# VS1005-Pico_2024-02-05.net
KiCad netlist of a schematic drawn in Altium Designer
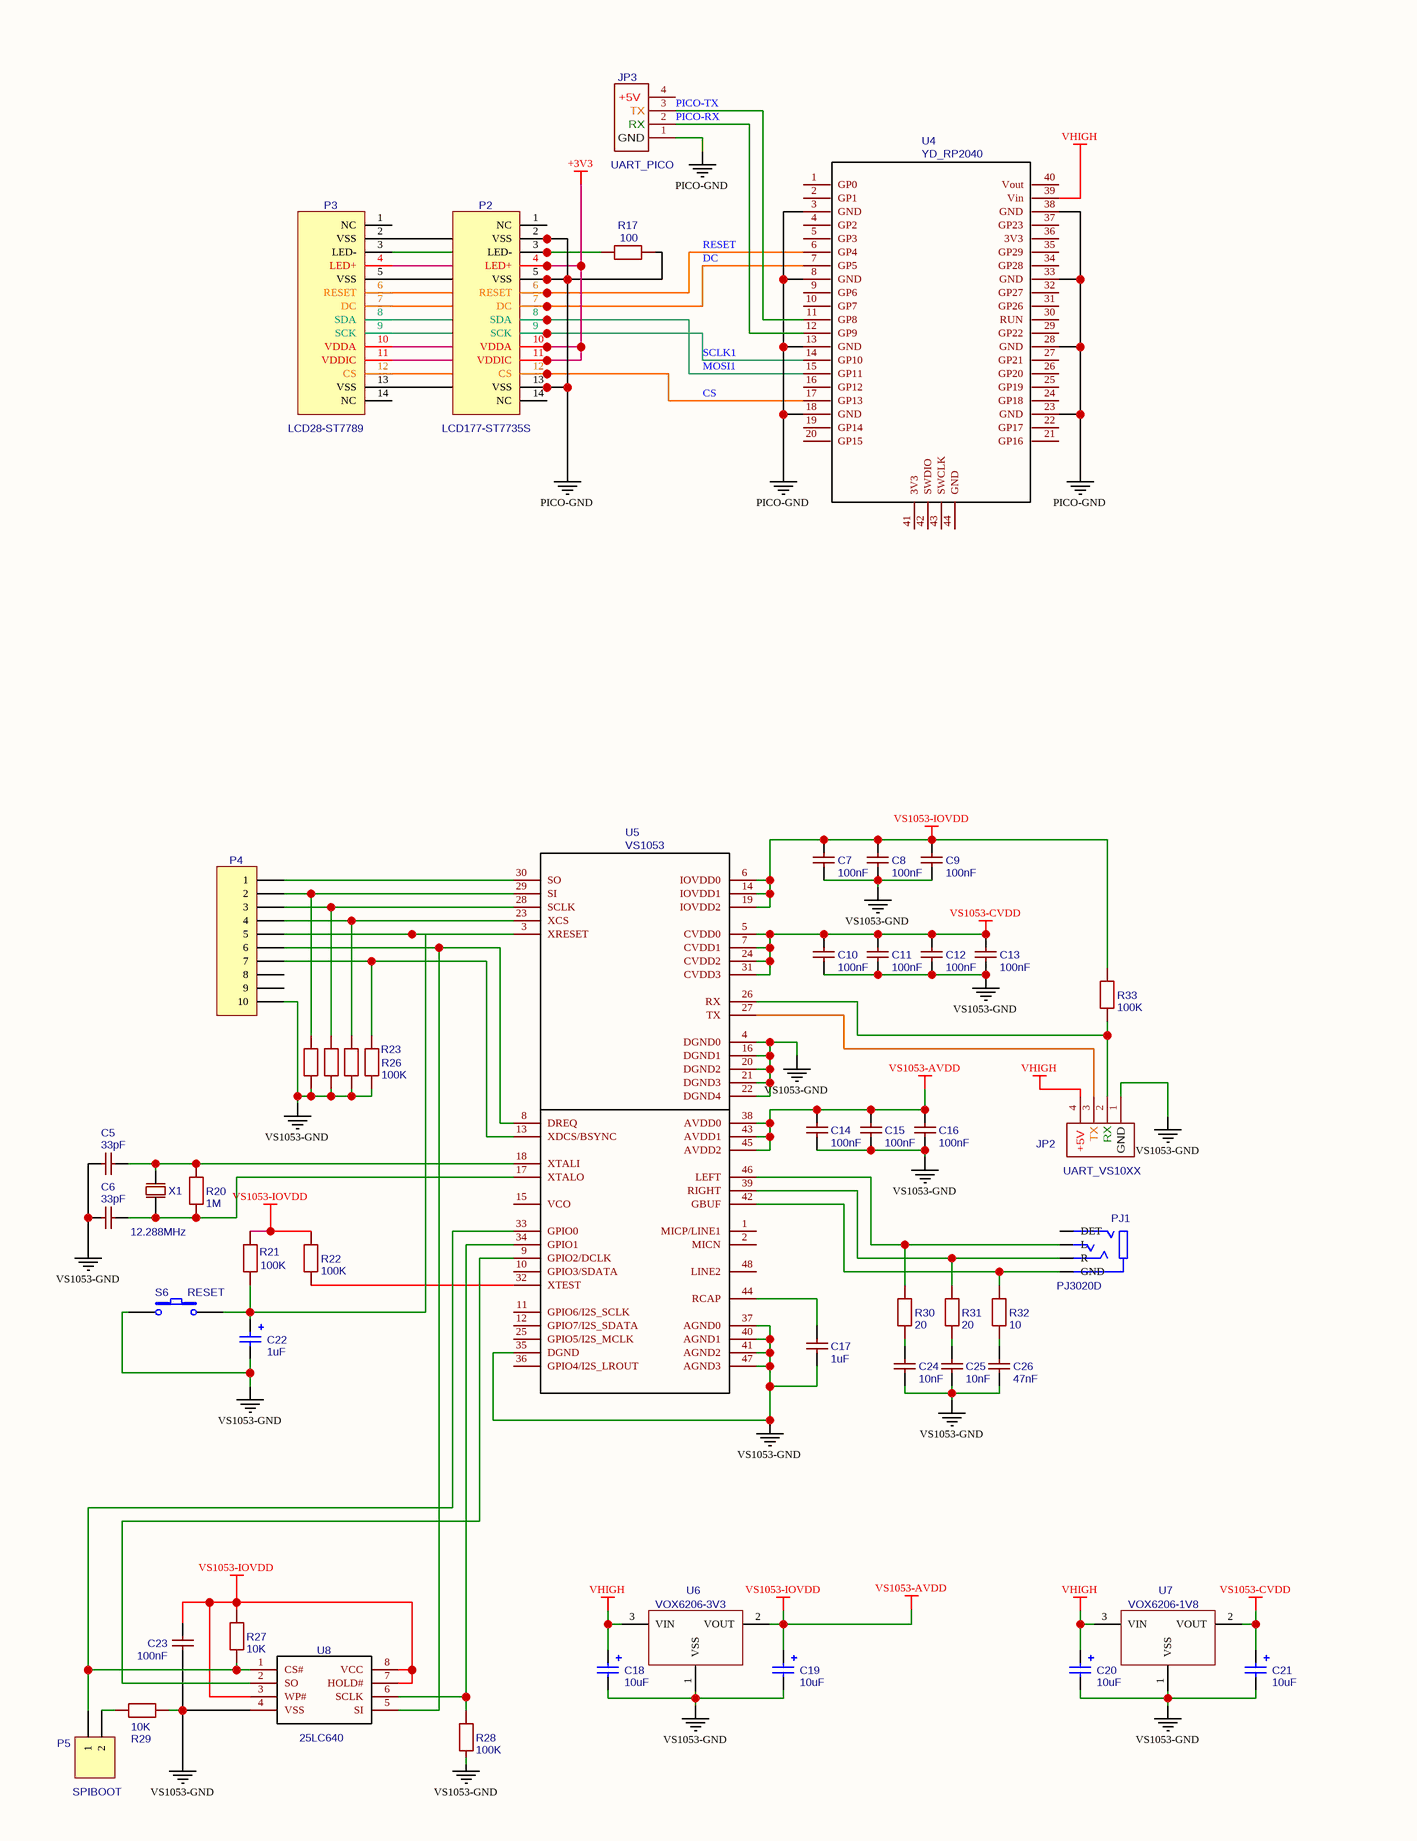
[diagram p0: VS1005-Pico_2024-02-05.schdoc, left]
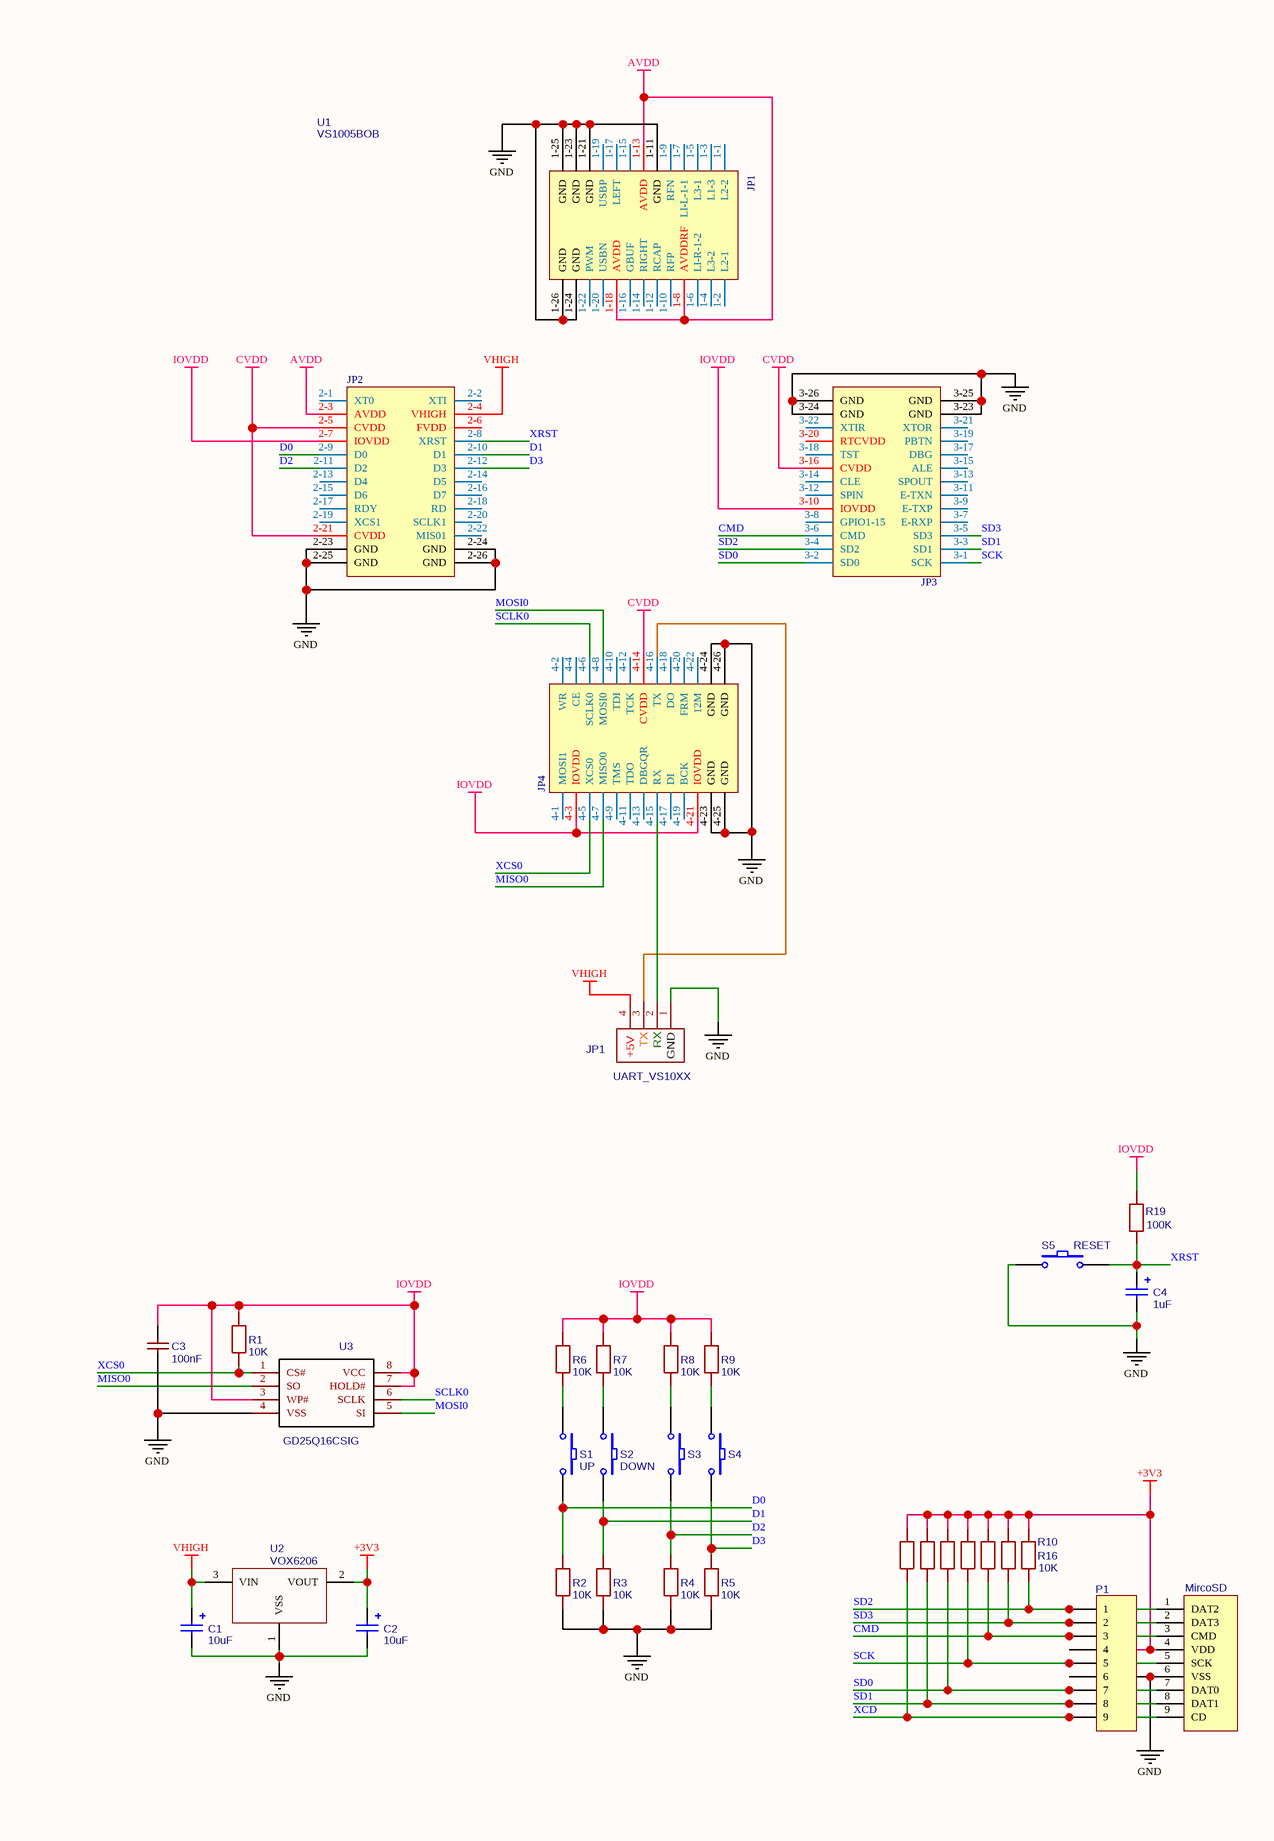
[diagram p1: VS1005-Pico_2024-02-05.schdoc, right]

(export (version "E")
  (design (tool "Eeschema 10.0.6"))
  (components
    (comp (ref "C1")
      (value "10uF")
      (fields (field (name "PUBLISHER") "Altium Limited") (field (name "CONTRIBUTOR") "kmok163"))
      (libsource (lib "altium-import") (part "root_0_10uF_"))
    )
    (comp (ref "C2")
      (value "10uF")
      (fields (field (name "PUBLISHER") "Altium Limited") (field (name "CONTRIBUTOR") "kmok163"))
      (libsource (lib "altium-import") (part "root_0_10uF_"))
    )
    (comp (ref "C3")
      (value "100nF")
      (fields
        (field (name "MANUFACTURER PART") "CC0805KRX7R9BB104")
        (field (name "MANUFACTURER") "YAGEO")
        (field (name "CONTRIBUTOR") "fen-1")
      )
      (libsource (lib "altium-import") (part "root_3_100nF_"))
    )
    (comp (ref "C4")
      (value "1uF")
      (fields (field (name "PUBLISHER") "Altium Limited") (field (name "CONTRIBUTOR") "kmok163"))
      (libsource (lib "altium-import") (part "root_0_1uF_"))
    )
    (comp (ref "C5")
      (value "33pF")
      (fields
        (field (name "MANUFACTURER PART") "CC0805KRX7R9BB104")
        (field (name "MANUFACTURER") "YAGEO")
        (field (name "CONTRIBUTOR") "fen-1")
      )
      (libsource (lib "altium-import") (part "root_2_33pF_"))
    )
    (comp (ref "C6")
      (value "33pF")
      (fields
        (field (name "MANUFACTURER PART") "CC0805KRX7R9BB104")
        (field (name "MANUFACTURER") "YAGEO")
        (field (name "CONTRIBUTOR") "fen-1")
      )
      (libsource (lib "altium-import") (part "root_2_33pF_"))
    )
    (comp (ref "C7")
      (value "100nF")
      (fields
        (field (name "MANUFACTURER PART") "CC0805KRX7R9BB104")
        (field (name "MANUFACTURER") "YAGEO")
        (field (name "CONTRIBUTOR") "fen-1")
      )
      (libsource (lib "altium-import") (part "root_3_100nF_"))
    )
    (comp (ref "C8")
      (value "100nF")
      (fields
        (field (name "MANUFACTURER PART") "CC0805KRX7R9BB104")
        (field (name "MANUFACTURER") "YAGEO")
        (field (name "CONTRIBUTOR") "fen-1")
      )
      (libsource (lib "altium-import") (part "root_3_100nF_"))
    )
    (comp (ref "C9")
      (value "100nF")
      (fields
        (field (name "MANUFACTURER PART") "CC0805KRX7R9BB104")
        (field (name "MANUFACTURER") "YAGEO")
        (field (name "CONTRIBUTOR") "fen-1")
      )
      (libsource (lib "altium-import") (part "root_3_100nF_"))
    )
    (comp (ref "C10")
      (value "100nF")
      (fields
        (field (name "MANUFACTURER PART") "CC0805KRX7R9BB104")
        (field (name "MANUFACTURER") "YAGEO")
        (field (name "CONTRIBUTOR") "fen-1")
      )
      (libsource (lib "altium-import") (part "root_3_100nF_"))
    )
    (comp (ref "C11")
      (value "100nF")
      (fields
        (field (name "MANUFACTURER PART") "CC0805KRX7R9BB104")
        (field (name "MANUFACTURER") "YAGEO")
        (field (name "CONTRIBUTOR") "fen-1")
      )
      (libsource (lib "altium-import") (part "root_3_100nF_"))
    )
    (comp (ref "C12")
      (value "100nF")
      (fields
        (field (name "MANUFACTURER PART") "CC0805KRX7R9BB104")
        (field (name "MANUFACTURER") "YAGEO")
        (field (name "CONTRIBUTOR") "fen-1")
      )
      (libsource (lib "altium-import") (part "root_3_100nF_"))
    )
    (comp (ref "C13")
      (value "100nF")
      (fields
        (field (name "MANUFACTURER PART") "CC0805KRX7R9BB104")
        (field (name "MANUFACTURER") "YAGEO")
        (field (name "CONTRIBUTOR") "fen-1")
      )
      (libsource (lib "altium-import") (part "root_3_100nF_"))
    )
    (comp (ref "C14")
      (value "100nF")
      (fields
        (field (name "MANUFACTURER PART") "CC0805KRX7R9BB104")
        (field (name "MANUFACTURER") "YAGEO")
        (field (name "CONTRIBUTOR") "fen-1")
      )
      (libsource (lib "altium-import") (part "root_3_100nF_"))
    )
    (comp (ref "C15")
      (value "100nF")
      (fields
        (field (name "MANUFACTURER PART") "CC0805KRX7R9BB104")
        (field (name "MANUFACTURER") "YAGEO")
        (field (name "CONTRIBUTOR") "fen-1")
      )
      (libsource (lib "altium-import") (part "root_3_100nF_"))
    )
    (comp (ref "C16")
      (value "100nF")
      (fields
        (field (name "MANUFACTURER PART") "CC0805KRX7R9BB104")
        (field (name "MANUFACTURER") "YAGEO")
        (field (name "CONTRIBUTOR") "fen-1")
      )
      (libsource (lib "altium-import") (part "root_3_100nF_"))
    )
    (comp (ref "C17")
      (value "1uF")
      (fields
        (field (name "MANUFACTURER PART") "CC0805KRX7R9BB104")
        (field (name "MANUFACTURER") "YAGEO")
        (field (name "CONTRIBUTOR") "fen-1")
      )
      (libsource (lib "altium-import") (part "root_3_1uF_"))
    )
    (comp (ref "C18")
      (value "10uF")
      (fields (field (name "PUBLISHER") "Altium Limited") (field (name "CONTRIBUTOR") "kmok163"))
      (libsource (lib "altium-import") (part "root_0_10uF_"))
    )
    (comp (ref "C19")
      (value "10uF")
      (fields (field (name "PUBLISHER") "Altium Limited") (field (name "CONTRIBUTOR") "kmok163"))
      (libsource (lib "altium-import") (part "root_0_10uF_"))
    )
    (comp (ref "C20")
      (value "10uF")
      (fields (field (name "PUBLISHER") "Altium Limited") (field (name "CONTRIBUTOR") "kmok163"))
      (libsource (lib "altium-import") (part "root_0_10uF_"))
    )
    (comp (ref "C21")
      (value "10uF")
      (fields (field (name "PUBLISHER") "Altium Limited") (field (name "CONTRIBUTOR") "kmok163"))
      (libsource (lib "altium-import") (part "root_0_10uF_"))
    )
    (comp (ref "C22")
      (value "1uF")
      (fields (field (name "PUBLISHER") "Altium Limited") (field (name "CONTRIBUTOR") "kmok163"))
      (libsource (lib "altium-import") (part "root_0_1uF_"))
    )
    (comp (ref "C23")
      (value "100nF")
      (fields
        (field (name "MANUFACTURER PART") "CC0805KRX7R9BB104")
        (field (name "MANUFACTURER") "YAGEO")
        (field (name "CONTRIBUTOR") "fen-1")
      )
      (libsource (lib "") (part "root_3_100nF__1"))
    )
    (comp (ref "C24")
      (value "10nF")
      (fields
        (field (name "MANUFACTURER PART") "CC0805KRX7R9BB104")
        (field (name "MANUFACTURER") "YAGEO")
        (field (name "CONTRIBUTOR") "fen-1")
      )
      (libsource (lib "altium-import") (part "root_3_10nF_"))
    )
    (comp (ref "C25")
      (value "10nF")
      (fields
        (field (name "MANUFACTURER PART") "CC0805KRX7R9BB104")
        (field (name "MANUFACTURER") "YAGEO")
        (field (name "CONTRIBUTOR") "fen-1")
      )
      (libsource (lib "altium-import") (part "root_3_10nF_"))
    )
    (comp (ref "C26")
      (value "47nF")
      (fields
        (field (name "MANUFACTURER PART") "CC0805KRX7R9BB104")
        (field (name "MANUFACTURER") "YAGEO")
        (field (name "CONTRIBUTOR") "fen-1")
      )
      (libsource (lib "altium-import") (part "root_3_47nF_"))
    )
    (comp (ref "JP1")
      (value "UART_VS10XX")
      (description "Header 4")
      (fields (field (name "CONTRIBUTOR") "SparkFun"))
      (libsource (lib "altium-import") (part "root_1_UART_VS10XX_"))
    )
    (comp (ref "JP2")
      (value "UART_VS10XX")
      (description "Header 4")
      (fields (field (name "CONTRIBUTOR") "SparkFun"))
      (libsource (lib "altium-import") (part "root_1_UART_VS10XX_"))
    )
    (comp (ref "JP3")
      (value "UART_PICO")
      (description "Header 4")
      (fields (field (name "CONTRIBUTOR") "SparkFun"))
      (libsource (lib "altium-import") (part "root_0_UART_PICO_"))
    )
    (comp (ref "P1")
      (value "Header 9")
      (fields (field (name "PUBLISHER") "Altium Limited") (field (name "CONTRIBUTOR") "kmok163"))
      (libsource (lib "altium-import") (part "root_0_Header 9_"))
    )
    (comp (ref "P2")
      (value "LCD177-ST7735S")
      (fields (field (name "PUBLISHER") "Altium Limited") (field (name "CONTRIBUTOR") "kmok163"))
      (libsource (lib "altium-import") (part "root_0_LCD177-ST7735S_"))
    )
    (comp (ref "P3")
      (value "LCD28-ST7789")
      (fields (field (name "PUBLISHER") "Altium Limited") (field (name "CONTRIBUTOR") "kmok163"))
      (libsource (lib "altium-import") (part "root_0_LCD28-ST7789_"))
    )
    (comp (ref "P4")
      (value "Header 10")
      (fields (field (name "PUBLISHER") "Altium Limited") (field (name "CONTRIBUTOR") "kmok163"))
      (libsource (lib "altium-import") (part "root_0_Header 10_"))
    )
    (comp (ref "P5")
      (value "SPIBOOT")
      (fields (field (name "PUBLISHER") "Altium Limited") (field (name "CONTRIBUTOR") "kmok163"))
      (libsource (lib "altium-import") (part "root_3_SPIBOOT_"))
    )
    (comp (ref "P6")
      (value "MircoSD")
      (fields (field (name "PUBLISHER") "Altium Limited") (field (name "CONTRIBUTOR") "kmok163"))
      (libsource (lib "altium-import") (part "root_0_MircoSD_"))
    )
    (comp (ref "PJ1")
      (value "PJ3020D")
      (fields (field (name "CONTRIBUTOR") "爱迪声DTS音响"))
      (libsource (lib "altium-import") (part "root_0_PJ3020D_"))
    )
    (comp (ref "R1")
      (value "10K")
      (fields (field (name "CONTRIBUTOR") "EDAUSER001"))
      (libsource (lib "altium-import") (part "root_1_10K_"))
    )
    (comp (ref "R2")
      (value "10K")
      (fields (field (name "CONTRIBUTOR") "EDAUSER001"))
      (libsource (lib "altium-import") (part "root_1_10K_"))
    )
    (comp (ref "R3")
      (value "10K")
      (fields (field (name "CONTRIBUTOR") "EDAUSER001"))
      (libsource (lib "altium-import") (part "root_1_10K_"))
    )
    (comp (ref "R4")
      (value "10K")
      (fields (field (name "CONTRIBUTOR") "EDAUSER001"))
      (libsource (lib "altium-import") (part "root_1_10K_"))
    )
    (comp (ref "R5")
      (value "10K")
      (fields (field (name "CONTRIBUTOR") "EDAUSER001"))
      (libsource (lib "altium-import") (part "root_1_10K_"))
    )
    (comp (ref "R6")
      (value "10K")
      (fields (field (name "CONTRIBUTOR") "EDAUSER001"))
      (libsource (lib "altium-import") (part "root_1_10K_"))
    )
    (comp (ref "R7")
      (value "10K")
      (fields (field (name "CONTRIBUTOR") "EDAUSER001"))
      (libsource (lib "altium-import") (part "root_1_10K_"))
    )
    (comp (ref "R8")
      (value "10K")
      (fields (field (name "CONTRIBUTOR") "EDAUSER001"))
      (libsource (lib "altium-import") (part "root_1_10K_"))
    )
    (comp (ref "R9")
      (value "10K")
      (fields (field (name "CONTRIBUTOR") "EDAUSER001"))
      (libsource (lib "altium-import") (part "root_1_10K_"))
    )
    (comp (ref "R10")
      (value "10K")
      (fields (field (name "CONTRIBUTOR") "EDAUSER001"))
      (libsource (lib "altium-import") (part "root_1_10K_"))
    )
    (comp (ref "R11")
      (value "10K")
      (fields (field (name "CONTRIBUTOR") "EDAUSER001"))
      (libsource (lib "altium-import") (part "root_1_10K_"))
    )
    (comp (ref "R12")
      (value "10K")
      (fields (field (name "CONTRIBUTOR") "EDAUSER001"))
      (libsource (lib "altium-import") (part "root_1_10K_"))
    )
    (comp (ref "R13")
      (value "10K")
      (fields (field (name "CONTRIBUTOR") "EDAUSER001"))
      (libsource (lib "altium-import") (part "root_1_10K_"))
    )
    (comp (ref "R14")
      (value "10K")
      (fields (field (name "CONTRIBUTOR") "EDAUSER001"))
      (libsource (lib "altium-import") (part "root_1_10K_"))
    )
    (comp (ref "R15")
      (value "10K")
      (fields (field (name "CONTRIBUTOR") "EDAUSER001"))
      (libsource (lib "altium-import") (part "root_1_10K_"))
    )
    (comp (ref "R16")
      (value "10K")
      (fields (field (name "CONTRIBUTOR") "EDAUSER001"))
      (libsource (lib "altium-import") (part "root_1_10K_"))
    )
    (comp (ref "R17")
      (value "100")
      (fields (field (name "CONTRIBUTOR") "EDAUSER001"))
      (libsource (lib "altium-import") (part "root_0_100_"))
    )
    (comp (ref "R19")
      (value "100K")
      (fields (field (name "CONTRIBUTOR") "EDAUSER001"))
      (libsource (lib "altium-import") (part "root_1_100K_"))
    )
    (comp (ref "R20")
      (value "1M")
      (fields (field (name "CONTRIBUTOR") "EDAUSER001"))
      (libsource (lib "altium-import") (part "root_1_1M_"))
    )
    (comp (ref "R21")
      (value "100K")
      (fields (field (name "CONTRIBUTOR") "EDAUSER001"))
      (libsource (lib "altium-import") (part "root_1_100K_"))
    )
    (comp (ref "R22")
      (value "100K")
      (fields (field (name "CONTRIBUTOR") "EDAUSER001"))
      (libsource (lib "altium-import") (part "root_1_100K_"))
    )
    (comp (ref "R23")
      (value "100K")
      (fields (field (name "CONTRIBUTOR") "EDAUSER001"))
      (libsource (lib "altium-import") (part "root_1_100K_"))
    )
    (comp (ref "R24")
      (value "100K")
      (fields (field (name "CONTRIBUTOR") "EDAUSER001"))
      (libsource (lib "altium-import") (part "root_1_100K_"))
    )
    (comp (ref "R25")
      (value "100K")
      (fields (field (name "CONTRIBUTOR") "EDAUSER001"))
      (libsource (lib "altium-import") (part "root_1_100K_"))
    )
    (comp (ref "R26")
      (value "100K")
      (fields (field (name "CONTRIBUTOR") "EDAUSER001"))
      (libsource (lib "altium-import") (part "root_1_100K_"))
    )
    (comp (ref "R27")
      (value "10K")
      (fields (field (name "CONTRIBUTOR") "EDAUSER001"))
      (libsource (lib "altium-import") (part "root_1_10K_"))
    )
    (comp (ref "R28")
      (value "100K")
      (fields (field (name "CONTRIBUTOR") "EDAUSER001"))
      (libsource (lib "altium-import") (part "root_1_100K_"))
    )
    (comp (ref "R29")
      (value "10K")
      (fields (field (name "CONTRIBUTOR") "EDAUSER001"))
      (libsource (lib "altium-import") (part "root_2_10K_"))
    )
    (comp (ref "R30")
      (value "20")
      (fields (field (name "CONTRIBUTOR") "EDAUSER001"))
      (libsource (lib "altium-import") (part "root_1_20_"))
    )
    (comp (ref "R31")
      (value "20")
      (fields (field (name "CONTRIBUTOR") "EDAUSER001"))
      (libsource (lib "altium-import") (part "root_1_20_"))
    )
    (comp (ref "R32")
      (value "10")
      (fields (field (name "CONTRIBUTOR") "EDAUSER001"))
      (libsource (lib "altium-import") (part "root_1_10_"))
    )
    (comp (ref "R33")
      (value "100K")
      (fields (field (name "CONTRIBUTOR") "EDAUSER001"))
      (libsource (lib "altium-import") (part "root_1_100K_"))
    )
    (comp (ref "S1")
      (value "UP")
      (fields (field (name "PUBLISHER") "Altium Limited") (field (name "CONTRIBUTOR") "kmok163"))
      (libsource (lib "altium-import") (part "root_3_UP_"))
    )
    (comp (ref "S2")
      (value "DOWN")
      (fields (field (name "PUBLISHER") "Altium Limited") (field (name "CONTRIBUTOR") "kmok163"))
      (libsource (lib "altium-import") (part "root_3_DOWN_"))
    )
    (comp (ref "S3")
      (value "D2")
      (fields (field (name "PUBLISHER") "Altium Limited") (field (name "CONTRIBUTOR") "kmok163"))
      (libsource (lib "altium-import") (part "root_3_D2_"))
    )
    (comp (ref "S4")
      (value "D3")
      (fields (field (name "PUBLISHER") "Altium Limited") (field (name "CONTRIBUTOR") "kmok163"))
      (libsource (lib "altium-import") (part "root_3_D3_"))
    )
    (comp (ref "S5")
      (value "RESET")
      (fields (field (name "PUBLISHER") "Altium Limited") (field (name "CONTRIBUTOR") "kmok163"))
      (libsource (lib "altium-import") (part "root_0_RESET_"))
    )
    (comp (ref "S6")
      (value "RESET")
      (fields (field (name "PUBLISHER") "Altium Limited") (field (name "CONTRIBUTOR") "kmok163"))
      (libsource (lib "altium-import") (part "root_0_RESET_"))
    )
    (comp (ref "U1")
      (value "VS1005BOB")
      (fields (field (name "MANUFACTURER") "VLSI Solution Oy") (field (name "CONTRIBUTOR") "kmok163"))
      (libsource (lib "altium-import") (part "root_0_VS1005BOB_"))
    )
    (comp (ref "U2")
      (value "VOX6206")
      (fields (field (name "PUBLISHER") "Altium Limited") (field (name "CONTRIBUTOR") "kmok163"))
      (libsource (lib "altium-import") (part "root_0_VOX6206_"))
    )
    (comp (ref "U3")
      (value "GD25Q16CSIG")
      (fields (field (name "MANUFACTURER") "GigaDevice(兆易创新)"))
      (libsource (lib "altium-import") (part "root_0_GD25Q16CSIG_"))
    )
    (comp (ref "U4")
      (value "YD_RP2040")
      (fields (field (name "CONTRIBUTOR") "armxu"))
      (libsource (lib "altium-import") (part "root_0_YD_RP2040_"))
    )
    (comp (ref "U5")
      (value "VS1053")
      (fields (field (name "MANUFACTURER") "VLSI Solution Oy") (field (name "CONTRIBUTOR") "kmok163"))
      (libsource (lib "altium-import") (part "root_0_VS1053_"))
    )
    (comp (ref "U6")
      (value "VOX6206-3V3")
      (fields (field (name "PUBLISHER") "Altium Limited") (field (name "CONTRIBUTOR") "kmok163"))
      (libsource (lib "altium-import") (part "root_0_VOX6206-3V3_"))
    )
    (comp (ref "U7")
      (value "VOX6206-1V8")
      (fields (field (name "PUBLISHER") "Altium Limited") (field (name "CONTRIBUTOR") "kmok163"))
      (libsource (lib "altium-import") (part "root_0_VOX6206-1V8_"))
    )
    (comp (ref "U8")
      (value "25LC640")
      (fields
        (field (name "MANUFACTURER") "GigaDevice(兆易创新)")
        (field (name "MANUFACTURER PART") "GD25Q16CSIG")
      )
      (libsource (lib "altium-import") (part "root_0_25LC640_"))
    )
    (comp (ref "X1")
      (value "12.288MHz")
      (fields
        (field (name "MANUFACTURER") "EPSON(爱普生)")
        (field (name "MANUFACTURER PART") "C-2 96.0000K-P:PBFREE")
        (field (name "CONTRIBUTOR") "lcsc")
      )
      (libsource (lib "altium-import") (part "root_1_12.288MHz_"))
    )
  )
  (nets
    (net (code "1") (name "+3V3") (class "Default")
      (node (ref "C2") (pin "1") (pinfunction "1_1") (pintype "passive"))
      (node (ref "P1") (pin "4") (pinfunction "4_4") (pintype "passive"))
      (node (ref "P2") (pin "10") (pinfunction "VDDA_10") (pintype "passive"))
      (node (ref "P2") (pin "11") (pinfunction "VDDIC_11") (pintype "passive"))
      (node (ref "P2") (pin "4") (pinfunction "LED+_4") (pintype "passive"))
      (node (ref "P3") (pin "10") (pinfunction "VDDA_10") (pintype "passive"))
      (node (ref "P3") (pin "11") (pinfunction "VDDIC_11") (pintype "passive"))
      (node (ref "P3") (pin "4") (pinfunction "LED+_4") (pintype "passive"))
      (node (ref "P6") (pin "4") (pinfunction "VDD_4") (pintype "passive"))
      (node (ref "R10") (pin "2") (pinfunction "2_2") (pintype "passive"))
      (node (ref "R11") (pin "2") (pinfunction "2_2") (pintype "passive"))
      (node (ref "R12") (pin "2") (pinfunction "2_2") (pintype "passive"))
      (node (ref "R13") (pin "2") (pinfunction "2_2") (pintype "passive"))
      (node (ref "R14") (pin "2") (pinfunction "2_2") (pintype "passive"))
      (node (ref "R15") (pin "2") (pinfunction "2_2") (pintype "passive"))
      (node (ref "R16") (pin "2") (pinfunction "2_2") (pintype "passive"))
      (node (ref "U2") (pin "2") (pinfunction "VOUT_2") (pintype "passive"))
    )
    (net (code "2") (name "/CMD") (class "Default")
      (node (ref "P1") (pin "3") (pinfunction "3_3") (pintype "passive"))
      (node (ref "P6") (pin "3") (pinfunction "CMD_3") (pintype "passive"))
      (node (ref "R14") (pin "1") (pinfunction "1_1") (pintype "passive"))
      (node (ref "U1") (pin "3-6") (pinfunction "CMD_3-6") (pintype "passive"))
    )
    (net (code "3") (name "/CS") (class "Default")
      (node (ref "P2") (pin "12") (pinfunction "CS_12") (pintype "passive"))
      (node (ref "P3") (pin "12") (pinfunction "CS_12") (pintype "passive"))
      (node (ref "U4") (pin "17") (pinfunction "GP13_17") (pintype "passive"))
    )
    (net (code "4") (name "/D0") (class "Default")
      (node (ref "R2") (pin "2") (pinfunction "2_2") (pintype "passive"))
      (node (ref "S1") (pin "2") (pinfunction "2_2") (pintype "passive"))
      (node (ref "U1") (pin "2-9") (pinfunction "D0_2-9") (pintype "passive"))
    )
    (net (code "5") (name "/D1") (class "Default")
      (node (ref "R3") (pin "2") (pinfunction "2_2") (pintype "passive"))
      (node (ref "S2") (pin "2") (pinfunction "2_2") (pintype "passive"))
      (node (ref "U1") (pin "2-10") (pinfunction "D1_2-10") (pintype "passive"))
    )
    (net (code "6") (name "/D2") (class "Default")
      (node (ref "R4") (pin "2") (pinfunction "2_2") (pintype "passive"))
      (node (ref "S3") (pin "2") (pinfunction "2_2") (pintype "passive"))
      (node (ref "U1") (pin "2-11") (pinfunction "D2_2-11") (pintype "passive"))
    )
    (net (code "7") (name "/D3") (class "Default")
      (node (ref "R5") (pin "2") (pinfunction "2_2") (pintype "passive"))
      (node (ref "S4") (pin "2") (pinfunction "2_2") (pintype "passive"))
      (node (ref "U1") (pin "2-12") (pinfunction "D3_2-12") (pintype "passive"))
    )
    (net (code "8") (name "/DC") (class "Default")
      (node (ref "P2") (pin "7") (pinfunction "DC_7") (pintype "passive"))
      (node (ref "P3") (pin "7") (pinfunction "DC_7") (pintype "passive"))
      (node (ref "U4") (pin "7") (pinfunction "GP5_7") (pintype "passive"))
    )
    (net (code "9") (name "/MISO0") (class "Default")
      (node (ref "U1") (pin "4-7") (pinfunction "MISO0_4-7") (pintype "passive"))
      (node (ref "U3") (pin "2") (pinfunction "SO_2") (pintype "passive"))
    )
    (net (code "10") (name "/MOSI0") (class "Default")
      (node (ref "U1") (pin "4-8") (pinfunction "MOSI0_4-8") (pintype "passive"))
      (node (ref "U3") (pin "5") (pinfunction "SI_5") (pintype "passive"))
    )
    (net (code "11") (name "/MOSI1") (class "Default")
      (node (ref "P2") (pin "8") (pinfunction "SDA_8") (pintype "passive"))
      (node (ref "P3") (pin "8") (pinfunction "SDA_8") (pintype "passive"))
      (node (ref "U4") (pin "15") (pinfunction "GP11_15") (pintype "passive"))
    )
    (net (code "12") (name "/PICO-RX") (class "Default")
      (node (ref "JP3") (pin "2") (pinfunction "2_2") (pintype "passive"))
      (node (ref "U4") (pin "12") (pinfunction "GP9_12") (pintype "passive"))
    )
    (net (code "13") (name "/PICO-TX") (class "Default")
      (node (ref "JP3") (pin "3") (pinfunction "3_3") (pintype "passive"))
      (node (ref "U4") (pin "11") (pinfunction "GP8_11") (pintype "passive"))
    )
    (net (code "14") (name "/RESET") (class "Default")
      (node (ref "P2") (pin "6") (pinfunction "RESET_6") (pintype "passive"))
      (node (ref "P3") (pin "6") (pinfunction "RESET_6") (pintype "passive"))
      (node (ref "U4") (pin "6") (pinfunction "GP4_6") (pintype "passive"))
    )
    (net (code "15") (name "/SCK") (class "Default")
      (node (ref "P1") (pin "5") (pinfunction "5_5") (pintype "passive"))
      (node (ref "P6") (pin "5") (pinfunction "SCK_5") (pintype "passive"))
      (node (ref "R13") (pin "1") (pinfunction "1_1") (pintype "passive"))
      (node (ref "U1") (pin "3-1") (pinfunction "SCK_3-1") (pintype "passive"))
    )
    (net (code "16") (name "/SCLK0") (class "Default")
      (node (ref "U1") (pin "4-6") (pinfunction "SCLK0_4-6") (pintype "passive"))
      (node (ref "U3") (pin "6") (pinfunction "SCLK_6") (pintype "passive"))
    )
    (net (code "17") (name "/SCLK1") (class "Default")
      (node (ref "P2") (pin "9") (pinfunction "SCK_9") (pintype "passive"))
      (node (ref "P3") (pin "9") (pinfunction "SCK_9") (pintype "passive"))
      (node (ref "U4") (pin "14") (pinfunction "GP10_14") (pintype "passive"))
    )
    (net (code "18") (name "/SD0") (class "Default")
      (node (ref "P1") (pin "7") (pinfunction "7_7") (pintype "passive"))
      (node (ref "P6") (pin "7") (pinfunction "DAT0_7") (pintype "passive"))
      (node (ref "R12") (pin "1") (pinfunction "1_1") (pintype "passive"))
      (node (ref "U1") (pin "3-2") (pinfunction "SD0_3-2") (pintype "passive"))
    )
    (net (code "19") (name "/SD1") (class "Default")
      (node (ref "P1") (pin "8") (pinfunction "8_8") (pintype "passive"))
      (node (ref "P6") (pin "8") (pinfunction "DAT1_8") (pintype "passive"))
      (node (ref "R11") (pin "1") (pinfunction "1_1") (pintype "passive"))
      (node (ref "U1") (pin "3-3") (pinfunction "SD1_3-3") (pintype "passive"))
    )
    (net (code "20") (name "/SD2") (class "Default")
      (node (ref "P1") (pin "1") (pinfunction "1_1") (pintype "passive"))
      (node (ref "P6") (pin "1") (pinfunction "DAT2_1") (pintype "passive"))
      (node (ref "R16") (pin "1") (pinfunction "1_1") (pintype "passive"))
      (node (ref "U1") (pin "3-4") (pinfunction "SD2_3-4") (pintype "passive"))
    )
    (net (code "21") (name "/SD3") (class "Default")
      (node (ref "P1") (pin "2") (pinfunction "2_2") (pintype "passive"))
      (node (ref "P6") (pin "2") (pinfunction "DAT3_2") (pintype "passive"))
      (node (ref "R15") (pin "1") (pinfunction "1_1") (pintype "passive"))
      (node (ref "U1") (pin "3-5") (pinfunction "SD3_3-5") (pintype "passive"))
    )
    (net (code "22") (name "/XCD") (class "Default")
      (node (ref "P1") (pin "9") (pinfunction "9_9") (pintype "passive"))
      (node (ref "P6") (pin "9") (pinfunction "CD_9") (pintype "passive"))
      (node (ref "R10") (pin "1") (pinfunction "1_1") (pintype "passive"))
    )
    (net (code "23") (name "/XCS0") (class "Default")
      (node (ref "R1") (pin "1") (pinfunction "1_1") (pintype "passive"))
      (node (ref "U1") (pin "4-5") (pinfunction "XCS0_4-5") (pintype "passive"))
      (node (ref "U3") (pin "1") (pinfunction "CS#_1") (pintype "passive"))
    )
    (net (code "24") (name "/XRST") (class "Default")
      (node (ref "C4") (pin "1") (pinfunction "1_1") (pintype "passive"))
      (node (ref "R19") (pin "1") (pinfunction "1_1") (pintype "passive"))
      (node (ref "S5") (pin "2") (pinfunction "2_2") (pintype "passive"))
      (node (ref "U1") (pin "2-8") (pinfunction "XRST_2-8") (pintype "passive"))
    )
    (net (code "25") (name "AVDD") (class "Default")
      (node (ref "U1") (pin "1-13") (pinfunction "AVDD_1-13") (pintype "passive"))
      (node (ref "U1") (pin "1-18") (pinfunction "AVDD_1-18") (pintype "passive"))
      (node (ref "U1") (pin "1-8") (pinfunction "AVDDRF_1-8") (pintype "passive"))
      (node (ref "U1") (pin "2-3") (pinfunction "AVDD_2-3") (pintype "passive"))
    )
    (net (code "26") (name "CVDD") (class "Default")
      (node (ref "U1") (pin "2-21") (pinfunction "CVDD_2-21") (pintype "passive"))
      (node (ref "U1") (pin "2-5") (pinfunction "CVDD_2-5") (pintype "passive"))
      (node (ref "U1") (pin "3-16") (pinfunction "CVDD_3-16") (pintype "passive"))
      (node (ref "U1") (pin "4-14") (pinfunction "CVDD_4-14") (pintype "passive"))
    )
    (net (code "27") (name "GND") (class "Default")
      (node (ref "C1") (pin "2") (pinfunction "2_2") (pintype "passive"))
      (node (ref "C2") (pin "2") (pinfunction "2_2") (pintype "passive"))
      (node (ref "C3") (pin "2") (pinfunction "2_2") (pintype "passive"))
      (node (ref "C4") (pin "2") (pinfunction "2_2") (pintype "passive"))
      (node (ref "JP1") (pin "1") (pinfunction "1_1") (pintype "passive"))
      (node (ref "P1") (pin "6") (pinfunction "6_6") (pintype "passive"))
      (node (ref "P6") (pin "6") (pinfunction "VSS_6") (pintype "passive"))
      (node (ref "R2") (pin "1") (pinfunction "1_1") (pintype "passive"))
      (node (ref "R3") (pin "1") (pinfunction "1_1") (pintype "passive"))
      (node (ref "R4") (pin "1") (pinfunction "1_1") (pintype "passive"))
      (node (ref "R5") (pin "1") (pinfunction "1_1") (pintype "passive"))
      (node (ref "S5") (pin "1") (pinfunction "1_1") (pintype "passive"))
      (node (ref "U1") (pin "1-11") (pinfunction "GND_1-11") (pintype "passive"))
      (node (ref "U1") (pin "1-21") (pinfunction "GND_1-21") (pintype "passive"))
      (node (ref "U1") (pin "1-23") (pinfunction "GND_1-23") (pintype "passive"))
      (node (ref "U1") (pin "1-24") (pinfunction "GND_1-24") (pintype "passive"))
      (node (ref "U1") (pin "1-25") (pinfunction "GND_1-25") (pintype "passive"))
      (node (ref "U1") (pin "1-26") (pinfunction "GND_1-26") (pintype "passive"))
      (node (ref "U1") (pin "2-23") (pinfunction "GND_2-23") (pintype "passive"))
      (node (ref "U1") (pin "2-24") (pinfunction "GND_2-24") (pintype "passive"))
      (node (ref "U1") (pin "2-25") (pinfunction "GND_2-25") (pintype "passive"))
      (node (ref "U1") (pin "2-26") (pinfunction "GND_2-26") (pintype "passive"))
      (node (ref "U1") (pin "3-23") (pinfunction "GND_3-23") (pintype "passive"))
      (node (ref "U1") (pin "3-24") (pinfunction "GND_3-24") (pintype "passive"))
      (node (ref "U1") (pin "3-25") (pinfunction "GND_3-25") (pintype "passive"))
      (node (ref "U1") (pin "3-26") (pinfunction "GND_3-26") (pintype "passive"))
      (node (ref "U1") (pin "4-23") (pinfunction "GND_4-23") (pintype "passive"))
      (node (ref "U1") (pin "4-24") (pinfunction "GND_4-24") (pintype "passive"))
      (node (ref "U1") (pin "4-25") (pinfunction "GND_4-25") (pintype "passive"))
      (node (ref "U1") (pin "4-26") (pinfunction "GND_4-26") (pintype "passive"))
      (node (ref "U2") (pin "1") (pinfunction "VSS_1") (pintype "passive"))
      (node (ref "U3") (pin "4") (pinfunction "VSS_4") (pintype "passive"))
    )
    (net (code "28") (name "IOVDD") (class "Default")
      (node (ref "C3") (pin "1") (pinfunction "1_1") (pintype "passive"))
      (node (ref "R1") (pin "2") (pinfunction "2_2") (pintype "passive"))
      (node (ref "R19") (pin "2") (pinfunction "2_2") (pintype "passive"))
      (node (ref "R6") (pin "2") (pinfunction "2_2") (pintype "passive"))
      (node (ref "R7") (pin "2") (pinfunction "2_2") (pintype "passive"))
      (node (ref "R8") (pin "2") (pinfunction "2_2") (pintype "passive"))
      (node (ref "R9") (pin "2") (pinfunction "2_2") (pintype "passive"))
      (node (ref "U1") (pin "2-7") (pinfunction "IOVDD_2-7") (pintype "passive"))
      (node (ref "U1") (pin "3-10") (pinfunction "IOVDD_3-10") (pintype "passive"))
      (node (ref "U1") (pin "4-21") (pinfunction "IOVDD_4-21") (pintype "passive"))
      (node (ref "U1") (pin "4-3") (pinfunction "IOVDD_4-3") (pintype "passive"))
      (node (ref "U3") (pin "3") (pinfunction "WP#_3") (pintype "passive"))
      (node (ref "U3") (pin "7") (pinfunction "HOLD#_7") (pintype "passive"))
      (node (ref "U3") (pin "8") (pinfunction "VCC_8") (pintype "passive"))
    )
    (net (code "29") (name "Net-(C24-Pad1)") (class "Default")
      (node (ref "C24") (pin "1") (pinfunction "1_1") (pintype "passive"))
      (node (ref "R30") (pin "1") (pinfunction "1_1") (pintype "passive"))
    )
    (net (code "30") (name "Net-(C25-Pad1)") (class "Default")
      (node (ref "C25") (pin "1") (pinfunction "1_1") (pintype "passive"))
      (node (ref "R31") (pin "1") (pinfunction "1_1") (pintype "passive"))
    )
    (net (code "31") (name "Net-(C26-Pad1)") (class "Default")
      (node (ref "C26") (pin "1") (pinfunction "1_1") (pintype "passive"))
      (node (ref "R32") (pin "1") (pinfunction "1_1") (pintype "passive"))
    )
    (net (code "32") (name "Net-(P2-LED-)") (class "Default")
      (node (ref "P2") (pin "3") (pinfunction "LED-_3") (pintype "passive"))
      (node (ref "P3") (pin "3") (pinfunction "LED-_3") (pintype "passive"))
      (node (ref "R17") (pin "2") (pinfunction "2_2") (pintype "passive"))
    )
    (net (code "33") (name "Net-(P5-Pad2)") (class "Default")
      (node (ref "P5") (pin "2") (pinfunction "2_2") (pintype "passive"))
      (node (ref "R29") (pin "2") (pinfunction "2_2") (pintype "passive"))
    )
    (net (code "34") (name "Net-(PJ1-GND)") (class "Default")
      (node (ref "PJ1") (pin "5") (pinfunction "GND_5") (pintype "passive"))
      (node (ref "R32") (pin "2") (pinfunction "2_2") (pintype "passive"))
      (node (ref "U5") (pin "42") (pinfunction "GBUF_42") (pintype "passive"))
    )
    (net (code "35") (name "Net-(PJ1-L)") (class "Default")
      (node (ref "PJ1") (pin "4") (pinfunction "L_4") (pintype "passive"))
      (node (ref "R30") (pin "2") (pinfunction "2_2") (pintype "passive"))
      (node (ref "U5") (pin "46") (pinfunction "LEFT_46") (pintype "passive"))
    )
    (net (code "36") (name "Net-(PJ1-R)") (class "Default")
      (node (ref "PJ1") (pin "3") (pinfunction "R_3") (pintype "passive"))
      (node (ref "R31") (pin "2") (pinfunction "2_2") (pintype "passive"))
      (node (ref "U5") (pin "39") (pinfunction "RIGHT_39") (pintype "passive"))
    )
    (net (code "37") (name "Net-(R6-Pad1)") (class "Default")
      (node (ref "R6") (pin "1") (pinfunction "1_1") (pintype "passive"))
      (node (ref "S1") (pin "1") (pinfunction "1_1") (pintype "passive"))
    )
    (net (code "38") (name "Net-(R7-Pad1)") (class "Default")
      (node (ref "R7") (pin "1") (pinfunction "1_1") (pintype "passive"))
      (node (ref "S2") (pin "1") (pinfunction "1_1") (pintype "passive"))
    )
    (net (code "39") (name "Net-(R8-Pad1)") (class "Default")
      (node (ref "R8") (pin "1") (pinfunction "1_1") (pintype "passive"))
      (node (ref "S3") (pin "1") (pinfunction "1_1") (pintype "passive"))
    )
    (net (code "40") (name "Net-(R9-Pad1)") (class "Default")
      (node (ref "R9") (pin "1") (pinfunction "1_1") (pintype "passive"))
      (node (ref "S4") (pin "1") (pinfunction "1_1") (pintype "passive"))
    )
    (net (code "41") (name "Net-(U1-RX)") (class "Default")
      (node (ref "JP1") (pin "2") (pinfunction "2_2") (pintype "passive"))
      (node (ref "U1") (pin "4-15") (pinfunction "RX_4-15") (pintype "passive"))
    )
    (net (code "42") (name "Net-(U1-TX)") (class "Default")
      (node (ref "JP1") (pin "3") (pinfunction "3_3") (pintype "passive"))
      (node (ref "U1") (pin "4-16") (pinfunction "TX_4-16") (pintype "passive"))
    )
    (net (code "43") (name "Net-(U5-DREQ)") (class "Default")
      (node (ref "P4") (pin "6") (pinfunction "6_6") (pintype "passive"))
      (node (ref "U5") (pin "8") (pinfunction "DREQ_8") (pintype "passive"))
      (node (ref "U8") (pin "5") (pinfunction "SI_5") (pintype "passive"))
    )
    (net (code "44") (name "Net-(U5-GPIO0)") (class "Default")
      (node (ref "P5") (pin "1") (pinfunction "1_1") (pintype "passive"))
      (node (ref "R27") (pin "1") (pinfunction "1_1") (pintype "passive"))
      (node (ref "U5") (pin "33") (pinfunction "GPIO0_33") (pintype "passive"))
      (node (ref "U8") (pin "1") (pinfunction "CS#_1") (pintype "passive"))
    )
    (net (code "45") (name "Net-(U5-GPIO1)") (class "Default")
      (node (ref "R28") (pin "2") (pinfunction "2_2") (pintype "passive"))
      (node (ref "U5") (pin "34") (pinfunction "GPIO1_34") (pintype "passive"))
      (node (ref "U8") (pin "6") (pinfunction "SCLK_6") (pintype "passive"))
    )
    (net (code "46") (name "Net-(U5-GPIO2{slash}DCLK)") (class "Default")
      (node (ref "U5") (pin "9") (pinfunction "GPIO2/DCLK_9") (pintype "passive"))
      (node (ref "U8") (pin "2") (pinfunction "SO_2") (pintype "passive"))
    )
    (net (code "47") (name "Net-(U5-RCAP)") (class "Default")
      (node (ref "C17") (pin "1") (pinfunction "1_1") (pintype "passive"))
      (node (ref "U5") (pin "44") (pinfunction "RCAP_44") (pintype "passive"))
    )
    (net (code "48") (name "Net-(U5-RX)") (class "Default")
      (node (ref "JP2") (pin "2") (pinfunction "2_2") (pintype "passive"))
      (node (ref "R33") (pin "1") (pinfunction "1_1") (pintype "passive"))
      (node (ref "U5") (pin "26") (pinfunction "RX_26") (pintype "passive"))
    )
    (net (code "49") (name "Net-(U5-SCLK)") (class "Default")
      (node (ref "P4") (pin "3") (pinfunction "3_3") (pintype "passive"))
      (node (ref "R24") (pin "2") (pinfunction "2_2") (pintype "passive"))
      (node (ref "U5") (pin "28") (pinfunction "SCLK_28") (pintype "passive"))
    )
    (net (code "50") (name "Net-(U5-SI)") (class "Default")
      (node (ref "P4") (pin "2") (pinfunction "2_2") (pintype "passive"))
      (node (ref "R23") (pin "2") (pinfunction "2_2") (pintype "passive"))
      (node (ref "U5") (pin "29") (pinfunction "SI_29") (pintype "passive"))
    )
    (net (code "51") (name "Net-(U5-SO)") (class "Default")
      (node (ref "P4") (pin "1") (pinfunction "1_1") (pintype "passive"))
      (node (ref "U5") (pin "30") (pinfunction "SO_30") (pintype "passive"))
    )
    (net (code "52") (name "Net-(U5-TX)") (class "Default")
      (node (ref "JP2") (pin "3") (pinfunction "3_3") (pintype "passive"))
      (node (ref "U5") (pin "27") (pinfunction "TX_27") (pintype "passive"))
    )
    (net (code "53") (name "Net-(U5-XCS)") (class "Default")
      (node (ref "P4") (pin "4") (pinfunction "4_4") (pintype "passive"))
      (node (ref "R25") (pin "2") (pinfunction "2_2") (pintype "passive"))
      (node (ref "U5") (pin "23") (pinfunction "XCS_23") (pintype "passive"))
    )
    (net (code "54") (name "Net-(U5-XDCS{slash}BSYNC)") (class "Default")
      (node (ref "P4") (pin "7") (pinfunction "7_7") (pintype "passive"))
      (node (ref "R26") (pin "2") (pinfunction "2_2") (pintype "passive"))
      (node (ref "U5") (pin "13") (pinfunction "XDCS/BSYNC_13") (pintype "passive"))
    )
    (net (code "55") (name "Net-(U5-XRESET)") (class "Default")
      (node (ref "C22") (pin "1") (pinfunction "1_1") (pintype "passive"))
      (node (ref "P4") (pin "5") (pinfunction "5_5") (pintype "passive"))
      (node (ref "R21") (pin "1") (pinfunction "1_1") (pintype "passive"))
      (node (ref "S6") (pin "2") (pinfunction "2_2") (pintype "passive"))
      (node (ref "U5") (pin "3") (pinfunction "XRESET_3") (pintype "passive"))
    )
    (net (code "56") (name "Net-(U5-XTALI)") (class "Default")
      (node (ref "C5") (pin "1") (pinfunction "1_1") (pintype "passive"))
      (node (ref "R20") (pin "2") (pinfunction "2_2") (pintype "passive"))
      (node (ref "U5") (pin "18") (pinfunction "XTALI_18") (pintype "passive"))
      (node (ref "X1") (pin "2") (pinfunction "2_2") (pintype "passive"))
    )
    (net (code "57") (name "Net-(U5-XTALO)") (class "Default")
      (node (ref "C6") (pin "1") (pinfunction "1_1") (pintype "passive"))
      (node (ref "R20") (pin "1") (pinfunction "1_1") (pintype "passive"))
      (node (ref "U5") (pin "17") (pinfunction "XTALO_17") (pintype "passive"))
      (node (ref "X1") (pin "1") (pinfunction "1_1") (pintype "passive"))
    )
    (net (code "58") (name "Net-(U5-XTEST)") (class "Default")
      (node (ref "R22") (pin "1") (pinfunction "1_1") (pintype "passive"))
      (node (ref "U5") (pin "32") (pinfunction "XTEST_32") (pintype "passive"))
    )
    (net (code "59") (name "PICO-GND") (class "Default")
      (node (ref "JP3") (pin "1") (pinfunction "1_1") (pintype "passive"))
      (node (ref "P2") (pin "13") (pinfunction "VSS_13") (pintype "passive"))
      (node (ref "P2") (pin "2") (pinfunction "VSS_2") (pintype "passive"))
      (node (ref "P2") (pin "5") (pinfunction "VSS_5") (pintype "passive"))
      (node (ref "P3") (pin "13") (pinfunction "VSS_13") (pintype "passive"))
      (node (ref "P3") (pin "2") (pinfunction "VSS_2") (pintype "passive"))
      (node (ref "P3") (pin "5") (pinfunction "VSS_5") (pintype "passive"))
      (node (ref "R17") (pin "1") (pinfunction "1_1") (pintype "passive"))
      (node (ref "U4") (pin "13") (pinfunction "GND_13") (pintype "passive"))
      (node (ref "U4") (pin "18") (pinfunction "GND_18") (pintype "passive"))
      (node (ref "U4") (pin "23") (pinfunction "GND_23") (pintype "passive"))
      (node (ref "U4") (pin "28") (pinfunction "GND_28") (pintype "passive"))
      (node (ref "U4") (pin "3") (pinfunction "GND_3") (pintype "passive"))
      (node (ref "U4") (pin "33") (pinfunction "GND_33") (pintype "passive"))
      (node (ref "U4") (pin "38") (pinfunction "GND_38") (pintype "passive"))
      (node (ref "U4") (pin "8") (pinfunction "GND_8") (pintype "passive"))
    )
    (net (code "60") (name "VHIGH") (class "Default")
      (node (ref "C1") (pin "1") (pinfunction "1_1") (pintype "passive"))
      (node (ref "C18") (pin "1") (pinfunction "1_1") (pintype "passive"))
      (node (ref "C20") (pin "1") (pinfunction "1_1") (pintype "passive"))
      (node (ref "JP1") (pin "4") (pinfunction "4_4") (pintype "passive"))
      (node (ref "JP2") (pin "4") (pinfunction "4_4") (pintype "passive"))
      (node (ref "U1") (pin "2-4") (pinfunction "VHIGH_2-4") (pintype "passive"))
      (node (ref "U2") (pin "3") (pinfunction "VIN_3") (pintype "passive"))
      (node (ref "U4") (pin "39") (pinfunction "Vin_39") (pintype "passive"))
      (node (ref "U6") (pin "3") (pinfunction "VIN_3") (pintype "passive"))
      (node (ref "U7") (pin "3") (pinfunction "VIN_3") (pintype "passive"))
    )
    (net (code "61") (name "VS1053-AVDD") (class "Default")
      (node (ref "C14") (pin "1") (pinfunction "1_1") (pintype "passive"))
      (node (ref "C15") (pin "1") (pinfunction "1_1") (pintype "passive"))
      (node (ref "C16") (pin "1") (pinfunction "1_1") (pintype "passive"))
      (node (ref "C19") (pin "1") (pinfunction "1_1") (pintype "passive"))
      (node (ref "C23") (pin "1") (pinfunction "1_1") (pintype "passive"))
      (node (ref "C7") (pin "1") (pinfunction "1_1") (pintype "passive"))
      (node (ref "C8") (pin "1") (pinfunction "1_1") (pintype "passive"))
      (node (ref "C9") (pin "1") (pinfunction "1_1") (pintype "passive"))
      (node (ref "R21") (pin "2") (pinfunction "2_2") (pintype "passive"))
      (node (ref "R22") (pin "2") (pinfunction "2_2") (pintype "passive"))
      (node (ref "R27") (pin "2") (pinfunction "2_2") (pintype "passive"))
      (node (ref "R33") (pin "2") (pinfunction "2_2") (pintype "passive"))
      (node (ref "U5") (pin "14") (pinfunction "IOVDD1_14") (pintype "passive"))
      (node (ref "U5") (pin "19") (pinfunction "IOVDD2_19") (pintype "passive"))
      (node (ref "U5") (pin "38") (pinfunction "AVDD0_38") (pintype "passive"))
      (node (ref "U5") (pin "43") (pinfunction "AVDD1_43") (pintype "passive"))
      (node (ref "U5") (pin "45") (pinfunction "AVDD2_45") (pintype "passive"))
      (node (ref "U5") (pin "6") (pinfunction "IOVDD0_6") (pintype "passive"))
      (node (ref "U6") (pin "2") (pinfunction "VOUT_2") (pintype "passive"))
      (node (ref "U8") (pin "3") (pinfunction "WP#_3") (pintype "passive"))
      (node (ref "U8") (pin "7") (pinfunction "HOLD#_7") (pintype "passive"))
      (node (ref "U8") (pin "8") (pinfunction "VCC_8") (pintype "passive"))
    )
    (net (code "62") (name "VS1053-CVDD") (class "Default")
      (node (ref "C10") (pin "1") (pinfunction "1_1") (pintype "passive"))
      (node (ref "C11") (pin "1") (pinfunction "1_1") (pintype "passive"))
      (node (ref "C12") (pin "1") (pinfunction "1_1") (pintype "passive"))
      (node (ref "C13") (pin "1") (pinfunction "1_1") (pintype "passive"))
      (node (ref "C21") (pin "1") (pinfunction "1_1") (pintype "passive"))
      (node (ref "U5") (pin "24") (pinfunction "CVDD2_24") (pintype "passive"))
      (node (ref "U5") (pin "31") (pinfunction "CVDD3_31") (pintype "passive"))
      (node (ref "U5") (pin "5") (pinfunction "CVDD0_5") (pintype "passive"))
      (node (ref "U5") (pin "7") (pinfunction "CVDD1_7") (pintype "passive"))
      (node (ref "U7") (pin "2") (pinfunction "VOUT_2") (pintype "passive"))
    )
    (net (code "63") (name "VS1053-GND") (class "Default")
      (node (ref "C10") (pin "2") (pinfunction "2_2") (pintype "passive"))
      (node (ref "C11") (pin "2") (pinfunction "2_2") (pintype "passive"))
      (node (ref "C12") (pin "2") (pinfunction "2_2") (pintype "passive"))
      (node (ref "C13") (pin "2") (pinfunction "2_2") (pintype "passive"))
      (node (ref "C14") (pin "2") (pinfunction "2_2") (pintype "passive"))
      (node (ref "C15") (pin "2") (pinfunction "2_2") (pintype "passive"))
      (node (ref "C16") (pin "2") (pinfunction "2_2") (pintype "passive"))
      (node (ref "C17") (pin "2") (pinfunction "2_2") (pintype "passive"))
      (node (ref "C18") (pin "2") (pinfunction "2_2") (pintype "passive"))
      (node (ref "C19") (pin "2") (pinfunction "2_2") (pintype "passive"))
      (node (ref "C20") (pin "2") (pinfunction "2_2") (pintype "passive"))
      (node (ref "C21") (pin "2") (pinfunction "2_2") (pintype "passive"))
      (node (ref "C22") (pin "2") (pinfunction "2_2") (pintype "passive"))
      (node (ref "C23") (pin "2") (pinfunction "2_2") (pintype "passive"))
      (node (ref "C24") (pin "2") (pinfunction "2_2") (pintype "passive"))
      (node (ref "C25") (pin "2") (pinfunction "2_2") (pintype "passive"))
      (node (ref "C26") (pin "2") (pinfunction "2_2") (pintype "passive"))
      (node (ref "C5") (pin "2") (pinfunction "2_2") (pintype "passive"))
      (node (ref "C6") (pin "2") (pinfunction "2_2") (pintype "passive"))
      (node (ref "C7") (pin "2") (pinfunction "2_2") (pintype "passive"))
      (node (ref "C8") (pin "2") (pinfunction "2_2") (pintype "passive"))
      (node (ref "C9") (pin "2") (pinfunction "2_2") (pintype "passive"))
      (node (ref "JP2") (pin "1") (pinfunction "1_1") (pintype "passive"))
      (node (ref "P4") (pin "10") (pinfunction "10_10") (pintype "passive"))
      (node (ref "R23") (pin "1") (pinfunction "1_1") (pintype "passive"))
      (node (ref "R24") (pin "1") (pinfunction "1_1") (pintype "passive"))
      (node (ref "R25") (pin "1") (pinfunction "1_1") (pintype "passive"))
      (node (ref "R26") (pin "1") (pinfunction "1_1") (pintype "passive"))
      (node (ref "R28") (pin "1") (pinfunction "1_1") (pintype "passive"))
      (node (ref "R29") (pin "1") (pinfunction "1_1") (pintype "passive"))
      (node (ref "S6") (pin "1") (pinfunction "1_1") (pintype "passive"))
      (node (ref "U5") (pin "16") (pinfunction "DGND1_16") (pintype "passive"))
      (node (ref "U5") (pin "20") (pinfunction "DGND2_20") (pintype "passive"))
      (node (ref "U5") (pin "21") (pinfunction "DGND3_21") (pintype "passive"))
      (node (ref "U5") (pin "22") (pinfunction "DGND4_22") (pintype "passive"))
      (node (ref "U5") (pin "35") (pinfunction "DGND_35") (pintype "passive"))
      (node (ref "U5") (pin "37") (pinfunction "AGND0_37") (pintype "passive"))
      (node (ref "U5") (pin "4") (pinfunction "DGND0_4") (pintype "passive"))
      (node (ref "U5") (pin "40") (pinfunction "AGND1_40") (pintype "passive"))
      (node (ref "U5") (pin "41") (pinfunction "AGND2_41") (pintype "passive"))
      (node (ref "U5") (pin "47") (pinfunction "AGND3_47") (pintype "passive"))
      (node (ref "U6") (pin "1") (pinfunction "VSS_1") (pintype "passive"))
      (node (ref "U7") (pin "1") (pinfunction "VSS_1") (pintype "passive"))
      (node (ref "U8") (pin "4") (pinfunction "VSS_4") (pintype "passive"))
    )
    (net (code "64") (name "unconnected-(JP3-Pad4)") (class "Default")
      (node (ref "JP3") (pin "4") (pinfunction "4_4") (pintype "passive"))
    )
    (net (code "65") (name "unconnected-(P2-NC-Pad1)") (class "Default")
      (node (ref "P2") (pin "1") (pinfunction "NC_1") (pintype "passive"))
    )
    (net (code "66") (name "unconnected-(P2-NC-Pad14)") (class "Default")
      (node (ref "P2") (pin "14") (pinfunction "NC_14") (pintype "passive"))
    )
    (net (code "67") (name "unconnected-(P3-NC-Pad1)") (class "Default")
      (node (ref "P3") (pin "1") (pinfunction "NC_1") (pintype "passive"))
    )
    (net (code "68") (name "unconnected-(P3-NC-Pad14)") (class "Default")
      (node (ref "P3") (pin "14") (pinfunction "NC_14") (pintype "passive"))
    )
    (net (code "69") (name "unconnected-(P4-Pad8)") (class "Default")
      (node (ref "P4") (pin "8") (pinfunction "8_8") (pintype "passive"))
    )
    (net (code "70") (name "unconnected-(P4-Pad9)") (class "Default")
      (node (ref "P4") (pin "9") (pinfunction "9_9") (pintype "passive"))
    )
    (net (code "71") (name "unconnected-(PJ1-DET-Pad2)") (class "Default")
      (node (ref "PJ1") (pin "2") (pinfunction "DET_2") (pintype "passive"))
    )
    (net (code "72") (name "unconnected-(U1-12M-Pad4-22)") (class "Default")
      (node (ref "U1") (pin "4-22") (pinfunction "12M_4-22") (pintype "passive"))
    )
    (net (code "73") (name "unconnected-(U1-ALE-Pad3-15)") (class "Default")
      (node (ref "U1") (pin "3-15") (pinfunction "ALE_3-15") (pintype "passive"))
    )
    (net (code "74") (name "unconnected-(U1-BCK-Pad4-19)") (class "Default")
      (node (ref "U1") (pin "4-19") (pinfunction "BCK_4-19") (pintype "passive"))
    )
    (net (code "75") (name "unconnected-(U1-CE-Pad4-4)") (class "Default")
      (node (ref "U1") (pin "4-4") (pinfunction "CE_4-4") (pintype "passive"))
    )
    (net (code "76") (name "unconnected-(U1-CLE-Pad3-14)") (class "Default")
      (node (ref "U1") (pin "3-14") (pinfunction "CLE_3-14") (pintype "passive"))
    )
    (net (code "77") (name "unconnected-(U1-D4-Pad2-13)") (class "Default")
      (node (ref "U1") (pin "2-13") (pinfunction "D4_2-13") (pintype "passive"))
    )
    (net (code "78") (name "unconnected-(U1-D5-Pad2-14)") (class "Default")
      (node (ref "U1") (pin "2-14") (pinfunction "D5_2-14") (pintype "passive"))
    )
    (net (code "79") (name "unconnected-(U1-D6-Pad2-15)") (class "Default")
      (node (ref "U1") (pin "2-15") (pinfunction "D6_2-15") (pintype "passive"))
    )
    (net (code "80") (name "unconnected-(U1-D7-Pad2-16)") (class "Default")
      (node (ref "U1") (pin "2-16") (pinfunction "D7_2-16") (pintype "passive"))
    )
    (net (code "81") (name "unconnected-(U1-DBG-Pad3-17)") (class "Default")
      (node (ref "U1") (pin "3-17") (pinfunction "DBG_3-17") (pintype "passive"))
    )
    (net (code "82") (name "unconnected-(U1-DBGQR-Pad4-13)") (class "Default")
      (node (ref "U1") (pin "4-13") (pinfunction "DBGQR_4-13") (pintype "passive"))
    )
    (net (code "83") (name "unconnected-(U1-DI-Pad4-17)") (class "Default")
      (node (ref "U1") (pin "4-17") (pinfunction "DI_4-17") (pintype "passive"))
    )
    (net (code "84") (name "unconnected-(U1-DO-Pad4-18)") (class "Default")
      (node (ref "U1") (pin "4-18") (pinfunction "DO_4-18") (pintype "passive"))
    )
    (net (code "85") (name "unconnected-(U1-E-RXP-Pad3-7)") (class "Default")
      (node (ref "U1") (pin "3-7") (pinfunction "E-RXP_3-7") (pintype "passive"))
    )
    (net (code "86") (name "unconnected-(U1-E-TXN-Pad3-11)") (class "Default")
      (node (ref "U1") (pin "3-11") (pinfunction "E-TXN_3-11") (pintype "passive"))
    )
    (net (code "87") (name "unconnected-(U1-E-TXP-Pad3-9)") (class "Default")
      (node (ref "U1") (pin "3-9") (pinfunction "E-TXP_3-9") (pintype "passive"))
    )
    (net (code "88") (name "unconnected-(U1-FRM-Pad4-20)") (class "Default")
      (node (ref "U1") (pin "4-20") (pinfunction "FRM_4-20") (pintype "passive"))
    )
    (net (code "89") (name "unconnected-(U1-FVDD-Pad2-6)") (class "Default")
      (node (ref "U1") (pin "2-6") (pinfunction "FVDD_2-6") (pintype "passive"))
    )
    (net (code "90") (name "unconnected-(U1-GBUF-Pad1-16)") (class "Default")
      (node (ref "U1") (pin "1-16") (pinfunction "GBUF_1-16") (pintype "passive"))
    )
    (net (code "91") (name "unconnected-(U1-GPIO1-15-Pad3-8)") (class "Default")
      (node (ref "U1") (pin "3-8") (pinfunction "GPIO1-15_3-8") (pintype "passive"))
    )
    (net (code "92") (name "unconnected-(U1-L1-3-Pad1-3)") (class "Default")
      (node (ref "U1") (pin "1-3") (pinfunction "L1-3_1-3") (pintype "passive"))
    )
    (net (code "93") (name "unconnected-(U1-L2-1-Pad1-2)") (class "Default")
      (node (ref "U1") (pin "1-2") (pinfunction "L2-1_1-2") (pintype "passive"))
    )
    (net (code "94") (name "unconnected-(U1-L2-2-Pad1-1)") (class "Default")
      (node (ref "U1") (pin "1-1") (pinfunction "L2-2_1-1") (pintype "passive"))
    )
    (net (code "95") (name "unconnected-(U1-L3-1-Pad1-5)") (class "Default")
      (node (ref "U1") (pin "1-5") (pinfunction "L3-1_1-5") (pintype "passive"))
    )
    (net (code "96") (name "unconnected-(U1-L3-2-Pad1-4)") (class "Default")
      (node (ref "U1") (pin "1-4") (pinfunction "L3-2_1-4") (pintype "passive"))
    )
    (net (code "97") (name "unconnected-(U1-LEFT-Pad1-17)") (class "Default")
      (node (ref "U1") (pin "1-17") (pinfunction "LEFT_1-17") (pintype "passive"))
    )
    (net (code "98") (name "unconnected-(U1-LI-L-1-1-Pad1-7)") (class "Default")
      (node (ref "U1") (pin "1-7") (pinfunction "LI-L-1-1_1-7") (pintype "passive"))
    )
    (net (code "99") (name "unconnected-(U1-LI-R-1-2-Pad1-6)") (class "Default")
      (node (ref "U1") (pin "1-6") (pinfunction "LI-R-1-2_1-6") (pintype "passive"))
    )
    (net (code "100") (name "unconnected-(U1-MIS01-Pad2-22)") (class "Default")
      (node (ref "U1") (pin "2-22") (pinfunction "MIS01_2-22") (pintype "passive"))
    )
    (net (code "101") (name "unconnected-(U1-MOSI1-Pad4-1)") (class "Default")
      (node (ref "U1") (pin "4-1") (pinfunction "MOSI1_4-1") (pintype "passive"))
    )
    (net (code "102") (name "unconnected-(U1-PBTN-Pad3-19)") (class "Default")
      (node (ref "U1") (pin "3-19") (pinfunction "PBTN_3-19") (pintype "passive"))
    )
    (net (code "103") (name "unconnected-(U1-PWM-Pad1-22)") (class "Default")
      (node (ref "U1") (pin "1-22") (pinfunction "PWM_1-22") (pintype "passive"))
    )
    (net (code "104") (name "unconnected-(U1-Pad1-15)") (class "Default")
      (node (ref "U1") (pin "1-15") (pintype "passive"))
    )
    (net (code "105") (name "unconnected-(U1-RCAP-Pad1-12)") (class "Default")
      (node (ref "U1") (pin "1-12") (pinfunction "RCAP_1-12") (pintype "passive"))
    )
    (net (code "106") (name "unconnected-(U1-RD-Pad2-18)") (class "Default")
      (node (ref "U1") (pin "2-18") (pinfunction "RD_2-18") (pintype "passive"))
    )
    (net (code "107") (name "unconnected-(U1-RDY-Pad2-17)") (class "Default")
      (node (ref "U1") (pin "2-17") (pinfunction "RDY_2-17") (pintype "passive"))
    )
    (net (code "108") (name "unconnected-(U1-RFN-Pad1-9)") (class "Default")
      (node (ref "U1") (pin "1-9") (pinfunction "RFN_1-9") (pintype "passive"))
    )
    (net (code "109") (name "unconnected-(U1-RFP-Pad1-10)") (class "Default")
      (node (ref "U1") (pin "1-10") (pinfunction "RFP_1-10") (pintype "passive"))
    )
    (net (code "110") (name "unconnected-(U1-RIGHT-Pad1-14)") (class "Default")
      (node (ref "U1") (pin "1-14") (pinfunction "RIGHT_1-14") (pintype "passive"))
    )
    (net (code "111") (name "unconnected-(U1-RTCVDD-Pad3-20)") (class "Default")
      (node (ref "U1") (pin "3-20") (pinfunction "RTCVDD_3-20") (pintype "passive"))
    )
    (net (code "112") (name "unconnected-(U1-SCLK1-Pad2-20)") (class "Default")
      (node (ref "U1") (pin "2-20") (pinfunction "SCLK1_2-20") (pintype "passive"))
    )
    (net (code "113") (name "unconnected-(U1-SPIN-Pad3-12)") (class "Default")
      (node (ref "U1") (pin "3-12") (pinfunction "SPIN_3-12") (pintype "passive"))
    )
    (net (code "114") (name "unconnected-(U1-SPOUT-Pad3-13)") (class "Default")
      (node (ref "U1") (pin "3-13") (pinfunction "SPOUT_3-13") (pintype "passive"))
    )
    (net (code "115") (name "unconnected-(U1-TCK-Pad4-12)") (class "Default")
      (node (ref "U1") (pin "4-12") (pinfunction "TCK_4-12") (pintype "passive"))
    )
    (net (code "116") (name "unconnected-(U1-TDI-Pad4-10)") (class "Default")
      (node (ref "U1") (pin "4-10") (pinfunction "TDI_4-10") (pintype "passive"))
    )
    (net (code "117") (name "unconnected-(U1-TDO-Pad4-11)") (class "Default")
      (node (ref "U1") (pin "4-11") (pinfunction "TDO_4-11") (pintype "passive"))
    )
    (net (code "118") (name "unconnected-(U1-TMS-Pad4-9)") (class "Default")
      (node (ref "U1") (pin "4-9") (pinfunction "TMS_4-9") (pintype "passive"))
    )
    (net (code "119") (name "unconnected-(U1-TST-Pad3-18)") (class "Default")
      (node (ref "U1") (pin "3-18") (pinfunction "TST_3-18") (pintype "passive"))
    )
    (net (code "120") (name "unconnected-(U1-USBN-Pad1-20)") (class "Default")
      (node (ref "U1") (pin "1-20") (pinfunction "USBN_1-20") (pintype "passive"))
    )
    (net (code "121") (name "unconnected-(U1-USBP-Pad1-19)") (class "Default")
      (node (ref "U1") (pin "1-19") (pinfunction "USBP_1-19") (pintype "passive"))
    )
    (net (code "122") (name "unconnected-(U1-WR-Pad4-2)") (class "Default")
      (node (ref "U1") (pin "4-2") (pinfunction "WR_4-2") (pintype "passive"))
    )
    (net (code "123") (name "unconnected-(U1-XCS1-Pad2-19)") (class "Default")
      (node (ref "U1") (pin "2-19") (pinfunction "XCS1_2-19") (pintype "passive"))
    )
    (net (code "124") (name "unconnected-(U1-XT0-Pad2-1)") (class "Default")
      (node (ref "U1") (pin "2-1") (pinfunction "XT0_2-1") (pintype "passive"))
    )
    (net (code "125") (name "unconnected-(U1-XTI-Pad2-2)") (class "Default")
      (node (ref "U1") (pin "2-2") (pinfunction "XTI_2-2") (pintype "passive"))
    )
    (net (code "126") (name "unconnected-(U1-XTIR-Pad3-22)") (class "Default")
      (node (ref "U1") (pin "3-22") (pinfunction "XTIR_3-22") (pintype "passive"))
    )
    (net (code "127") (name "unconnected-(U1-XTOR-Pad3-21)") (class "Default")
      (node (ref "U1") (pin "3-21") (pinfunction "XTOR_3-21") (pintype "passive"))
    )
    (net (code "128") (name "unconnected-(U4-3V3-Pad36)") (class "Default")
      (node (ref "U4") (pin "36") (pinfunction "3V3_36") (pintype "passive"))
    )
    (net (code "129") (name "unconnected-(U4-3V3-Pad41)") (class "Default")
      (node (ref "U4") (pin "41") (pinfunction "3V3_41") (pintype "passive"))
    )
    (net (code "130") (name "unconnected-(U4-GND-Pad44)") (class "Default")
      (node (ref "U4") (pin "44") (pinfunction "GND_44") (pintype "passive"))
    )
    (net (code "131") (name "unconnected-(U4-GP0-Pad1)") (class "Default")
      (node (ref "U4") (pin "1") (pinfunction "GP0_1") (pintype "passive"))
    )
    (net (code "132") (name "unconnected-(U4-GP1-Pad2)") (class "Default")
      (node (ref "U4") (pin "2") (pinfunction "GP1_2") (pintype "passive"))
    )
    (net (code "133") (name "unconnected-(U4-GP2-Pad4)") (class "Default")
      (node (ref "U4") (pin "4") (pinfunction "GP2_4") (pintype "passive"))
    )
    (net (code "134") (name "unconnected-(U4-GP3-Pad5)") (class "Default")
      (node (ref "U4") (pin "5") (pinfunction "GP3_5") (pintype "passive"))
    )
    (net (code "135") (name "unconnected-(U4-GP6-Pad9)") (class "Default")
      (node (ref "U4") (pin "9") (pinfunction "GP6_9") (pintype "passive"))
    )
    (net (code "136") (name "unconnected-(U4-GP7-Pad10)") (class "Default")
      (node (ref "U4") (pin "10") (pinfunction "GP7_10") (pintype "passive"))
    )
    (net (code "137") (name "unconnected-(U4-GP12-Pad16)") (class "Default")
      (node (ref "U4") (pin "16") (pinfunction "GP12_16") (pintype "passive"))
    )
    (net (code "138") (name "unconnected-(U4-GP14-Pad19)") (class "Default")
      (node (ref "U4") (pin "19") (pinfunction "GP14_19") (pintype "passive"))
    )
    (net (code "139") (name "unconnected-(U4-GP15-Pad20)") (class "Default")
      (node (ref "U4") (pin "20") (pinfunction "GP15_20") (pintype "passive"))
    )
    (net (code "140") (name "unconnected-(U4-GP16-Pad21)") (class "Default")
      (node (ref "U4") (pin "21") (pinfunction "GP16_21") (pintype "passive"))
    )
    (net (code "141") (name "unconnected-(U4-GP17-Pad22)") (class "Default")
      (node (ref "U4") (pin "22") (pinfunction "GP17_22") (pintype "passive"))
    )
    (net (code "142") (name "unconnected-(U4-GP18-Pad24)") (class "Default")
      (node (ref "U4") (pin "24") (pinfunction "GP18_24") (pintype "passive"))
    )
    (net (code "143") (name "unconnected-(U4-GP19-Pad25)") (class "Default")
      (node (ref "U4") (pin "25") (pinfunction "GP19_25") (pintype "passive"))
    )
    (net (code "144") (name "unconnected-(U4-GP20-Pad26)") (class "Default")
      (node (ref "U4") (pin "26") (pinfunction "GP20_26") (pintype "passive"))
    )
    (net (code "145") (name "unconnected-(U4-GP21-Pad27)") (class "Default")
      (node (ref "U4") (pin "27") (pinfunction "GP21_27") (pintype "passive"))
    )
    (net (code "146") (name "unconnected-(U4-GP22-Pad29)") (class "Default")
      (node (ref "U4") (pin "29") (pinfunction "GP22_29") (pintype "passive"))
    )
    (net (code "147") (name "unconnected-(U4-GP23-Pad37)") (class "Default")
      (node (ref "U4") (pin "37") (pinfunction "GP23_37") (pintype "passive"))
    )
    (net (code "148") (name "unconnected-(U4-GP26-Pad31)") (class "Default")
      (node (ref "U4") (pin "31") (pinfunction "GP26_31") (pintype "passive"))
    )
    (net (code "149") (name "unconnected-(U4-GP27-Pad32)") (class "Default")
      (node (ref "U4") (pin "32") (pinfunction "GP27_32") (pintype "passive"))
    )
    (net (code "150") (name "unconnected-(U4-GP28-Pad34)") (class "Default")
      (node (ref "U4") (pin "34") (pinfunction "GP28_34") (pintype "passive"))
    )
    (net (code "151") (name "unconnected-(U4-GP29-Pad35)") (class "Default")
      (node (ref "U4") (pin "35") (pinfunction "GP29_35") (pintype "passive"))
    )
    (net (code "152") (name "unconnected-(U4-RUN-Pad30)") (class "Default")
      (node (ref "U4") (pin "30") (pinfunction "RUN_30") (pintype "passive"))
    )
    (net (code "153") (name "unconnected-(U4-SWCLK-Pad43)") (class "Default")
      (node (ref "U4") (pin "43") (pinfunction "SWCLK_43") (pintype "passive"))
    )
    (net (code "154") (name "unconnected-(U4-SWDIO-Pad42)") (class "Default")
      (node (ref "U4") (pin "42") (pinfunction "SWDIO_42") (pintype "passive"))
    )
    (net (code "155") (name "unconnected-(U4-Vout-Pad40)") (class "Default")
      (node (ref "U4") (pin "40") (pinfunction "Vout_40") (pintype "passive"))
    )
    (net (code "156") (name "unconnected-(U5-GPIO3{slash}SDATA-Pad10)") (class "Default")
      (node (ref "U5") (pin "10") (pinfunction "GPIO3/SDATA_10") (pintype "passive"))
    )
    (net (code "157") (name "unconnected-(U5-GPIO4{slash}I2S_LROUT-Pad36)") (class "Default")
      (node (ref "U5") (pin "36") (pinfunction "GPIO4/I2S_LROUT_36") (pintype "passive"))
    )
    (net (code "158") (name "unconnected-(U5-GPIO5{slash}I2S_MCLK-Pad25)") (class "Default")
      (node (ref "U5") (pin "25") (pinfunction "GPIO5/I2S_MCLK_25") (pintype "passive"))
    )
    (net (code "159") (name "unconnected-(U5-GPIO6{slash}I2S_SCLK-Pad11)") (class "Default")
      (node (ref "U5") (pin "11") (pinfunction "GPIO6/I2S_SCLK_11") (pintype "passive"))
    )
    (net (code "160") (name "unconnected-(U5-GPIO7{slash}I2S_SDATA-Pad12)") (class "Default")
      (node (ref "U5") (pin "12") (pinfunction "GPIO7/I2S_SDATA_12") (pintype "passive"))
    )
    (net (code "161") (name "unconnected-(U5-LINE2-Pad48)") (class "Default")
      (node (ref "U5") (pin "48") (pinfunction "LINE2_48") (pintype "passive"))
    )
    (net (code "162") (name "unconnected-(U5-MICN-Pad2)") (class "Default")
      (node (ref "U5") (pin "2") (pinfunction "MICN_2") (pintype "passive"))
    )
    (net (code "163") (name "unconnected-(U5-MICP{slash}LINE1-Pad1)") (class "Default")
      (node (ref "U5") (pin "1") (pinfunction "MICP/LINE1_1") (pintype "passive"))
    )
    (net (code "164") (name "unconnected-(U5-VCO-Pad15)") (class "Default")
      (node (ref "U5") (pin "15") (pinfunction "VCO_15") (pintype "passive"))
    )
  )
)
